# ANALOGv1_4.net
KiCad netlist of a schematic drawn in Altium Designer
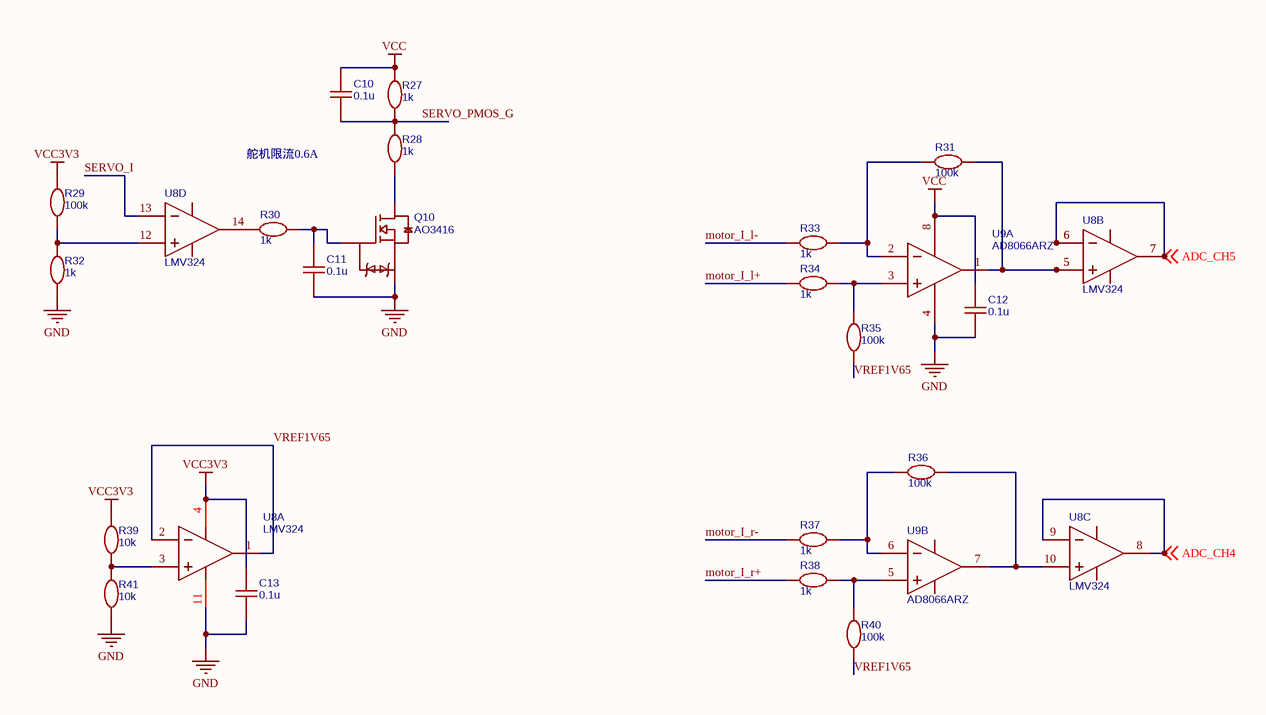
[diagram p0: ANALOGv1.4.SchDoc]

(export (version "E")
  (design (tool "Eeschema 10.0.6"))
  (components
    (comp (ref "C10")
      (value "0.1u")
      (footprint "C0603")
      (fields (field (name "CONTRIBUTOR") "LCEDA_Lib"))
      (libsource (lib "JLC") (part "C0603"))
    )
    (comp (ref "C11")
      (value "0.1u")
      (footprint "C0603")
      (fields (field (name "CONTRIBUTOR") "LCEDA_Lib"))
      (libsource (lib "JLC") (part "C0603"))
    )
    (comp (ref "C12")
      (value "0.1u")
      (footprint "C0603")
      (fields (field (name "CONTRIBUTOR") "LCEDA_Lib"))
      (libsource (lib "JLC") (part "C0603"))
    )
    (comp (ref "C13")
      (value "0.1u")
      (footprint "C0603")
      (fields (field (name "CONTRIBUTOR") "LCEDA_Lib"))
      (libsource (lib "JLC") (part "C0603"))
    )
    (comp (ref "Q10")
      (value "AO3416")
      (footprint "SOT-23-3_L2.9-W1.6-P1.90-LS2.8-BR")
      (fields (field (name "BOM_SUPPLIER PART") "C43307"))
      (libsource (lib "JLC") (part "AO3416"))
    )
    (comp (ref "R27")
      (value "1k")
      (footprint "R0603")
      (fields (field (name "CONTRIBUTOR") "LCEDA_Lib"))
      (libsource (lib "JLC") (part "R0603"))
    )
    (comp (ref "R28")
      (value "1k")
      (footprint "R0603")
      (fields (field (name "CONTRIBUTOR") "LCEDA_Lib"))
      (libsource (lib "JLC") (part "R0603"))
    )
    (comp (ref "R29")
      (value "100k")
      (footprint "R0603")
      (fields (field (name "CONTRIBUTOR") "LCEDA_Lib"))
      (libsource (lib "JLC") (part "R0603"))
    )
    (comp (ref "R30")
      (value "1k")
      (footprint "R0603")
      (fields (field (name "CONTRIBUTOR") "LCEDA_Lib"))
      (libsource (lib "JLC") (part "R0603"))
    )
    (comp (ref "R31")
      (value "100k")
      (footprint "R0603")
      (fields (field (name "CONTRIBUTOR") "LCEDA_Lib"))
      (libsource (lib "JLC") (part "R0603"))
    )
    (comp (ref "R32")
      (value "1k")
      (footprint "R0603")
      (fields (field (name "CONTRIBUTOR") "LCEDA_Lib"))
      (libsource (lib "JLC") (part "R0603"))
    )
    (comp (ref "R33")
      (value "1k")
      (footprint "R0603")
      (fields (field (name "CONTRIBUTOR") "LCEDA_Lib"))
      (libsource (lib "JLC") (part "R0603"))
    )
    (comp (ref "R34")
      (value "1k")
      (footprint "R0603")
      (fields (field (name "CONTRIBUTOR") "LCEDA_Lib"))
      (libsource (lib "JLC") (part "R0603"))
    )
    (comp (ref "R35")
      (value "100k")
      (footprint "R0603")
      (fields (field (name "CONTRIBUTOR") "LCEDA_Lib"))
      (libsource (lib "JLC") (part "R0603"))
    )
    (comp (ref "R36")
      (value "100k")
      (footprint "R0603")
      (fields (field (name "CONTRIBUTOR") "LCEDA_Lib"))
      (libsource (lib "JLC") (part "R0603"))
    )
    (comp (ref "R37")
      (value "1k")
      (footprint "R0603")
      (fields (field (name "CONTRIBUTOR") "LCEDA_Lib"))
      (libsource (lib "JLC") (part "R0603"))
    )
    (comp (ref "R38")
      (value "1k")
      (footprint "R0603")
      (fields (field (name "CONTRIBUTOR") "LCEDA_Lib"))
      (libsource (lib "JLC") (part "R0603"))
    )
    (comp (ref "R39")
      (value "10k")
      (footprint "R0603")
      (fields (field (name "CONTRIBUTOR") "LCEDA_Lib"))
      (libsource (lib "JLC") (part "R0603"))
    )
    (comp (ref "R40")
      (value "100k")
      (footprint "R0603")
      (fields (field (name "CONTRIBUTOR") "LCEDA_Lib"))
      (libsource (lib "JLC") (part "R0603"))
    )
    (comp (ref "R41")
      (value "10k")
      (footprint "R0603")
      (fields (field (name "CONTRIBUTOR") "LCEDA_Lib"))
      (libsource (lib "JLC") (part "R0603"))
    )
    (comp (ref "U8")
      (value "LMV324")
      (footprint "SOP-14_L8.6-W3.9-P1.27-LS6.0-BL")
      (fields (field (name "BOM_SUPPLIER PART") "C395458") (field (name "SUBPART_NO") "1"))
      (libsource (lib "") (part "LMV324_1"))
    )
    (comp (ref "U9")
      (value "AD8066ARZ")
      (footprint "SOIC-8_L5.0-W4.0-P1.27-LS6.0-BL")
      (fields (field (name "BOM_SUPPLIER PART") "C9647") (field (name "SUBPART_NO") "1"))
      (libsource (lib "JLC") (part "AD8066ARZ"))
    )
  )
  (nets
    (net (code "1") (name "/SERVO_I") (class "Default")
      (node (ref "U8") (pin "13") (pinfunction "4IN-_13") (pintype "passive"))
    )
    (net (code "2") (name "/SERVO_PMOS_G") (class "Default")
      (node (ref "C10") (pin "1") (pinfunction "1_1") (pintype "passive"))
      (node (ref "R27") (pin "1") (pinfunction "1_1") (pintype "passive"))
      (node (ref "R28") (pin "2") (pinfunction "2_2") (pintype "passive"))
    )
    (net (code "3") (name "/VREF1V65") (class "Default")
      (node (ref "R35") (pin "1") (pinfunction "1_1") (pintype "passive"))
      (node (ref "R40") (pin "1") (pinfunction "1_1") (pintype "passive"))
      (node (ref "U8") (pin "1") (pinfunction "1OUT_1") (pintype "passive"))
      (node (ref "U8") (pin "2") (pinfunction "1IN-_2") (pintype "passive"))
    )
    (net (code "4") (name "/motor_I_l+") (class "Default")
      (node (ref "R34") (pin "1") (pinfunction "1_1") (pintype "passive"))
    )
    (net (code "5") (name "/motor_I_l-") (class "Default")
      (node (ref "R33") (pin "1") (pinfunction "1_1") (pintype "passive"))
    )
    (net (code "6") (name "/motor_I_r+") (class "Default")
      (node (ref "R38") (pin "1") (pinfunction "1_1") (pintype "passive"))
    )
    (net (code "7") (name "/motor_I_r-") (class "Default")
      (node (ref "R37") (pin "1") (pinfunction "1_1") (pintype "passive"))
    )
    (net (code "8") (name "ADC_CH4") (class "Default")
      (node (ref "U8") (pin "8") (pinfunction "3OUT_8") (pintype "passive"))
      (node (ref "U8") (pin "9") (pinfunction "3IN-_9") (pintype "passive"))
    )
    (net (code "9") (name "ADC_CH5") (class "Default")
      (node (ref "U8") (pin "6") (pinfunction "2IN-_6") (pintype "passive"))
      (node (ref "U8") (pin "7") (pinfunction "2OUT_7") (pintype "passive"))
    )
    (net (code "10") (name "GND") (class "Default")
      (node (ref "C11") (pin "1") (pinfunction "1_1") (pintype "passive"))
      (node (ref "C12") (pin "1") (pinfunction "1_1") (pintype "passive"))
      (node (ref "C13") (pin "1") (pinfunction "1_1") (pintype "passive"))
      (node (ref "Q10") (pin "2") (pinfunction "S_2") (pintype "passive"))
      (node (ref "R32") (pin "1") (pinfunction "1_1") (pintype "passive"))
      (node (ref "R41") (pin "1") (pinfunction "1_1") (pintype "passive"))
      (node (ref "U8") (pin "11") (pinfunction "GND_11") (pintype "passive"))
      (node (ref "U9") (pin "4") (pinfunction "-VS_4") (pintype "passive"))
    )
    (net (code "11") (name "Net-(Q10-D)") (class "Default")
      (node (ref "Q10") (pin "3") (pinfunction "D_3") (pintype "passive"))
      (node (ref "R28") (pin "1") (pinfunction "1_1") (pintype "passive"))
    )
    (net (code "12") (name "Net-(Q10-G)") (class "Default")
      (node (ref "C11") (pin "2") (pinfunction "2_2") (pintype "passive"))
      (node (ref "Q10") (pin "1") (pinfunction "G_1") (pintype "passive"))
      (node (ref "R30") (pin "2") (pinfunction "2_2") (pintype "passive"))
    )
    (net (code "13") (name "Net-(U8A-1IN+)") (class "Default")
      (node (ref "R39") (pin "1") (pinfunction "1_1") (pintype "passive"))
      (node (ref "R41") (pin "2") (pinfunction "2_2") (pintype "passive"))
      (node (ref "U8") (pin "3") (pinfunction "1IN+_3") (pintype "passive"))
    )
    (net (code "14") (name "Net-(U8B-2IN+)") (class "Default")
      (node (ref "R31") (pin "2") (pinfunction "2_2") (pintype "passive"))
      (node (ref "U8") (pin "5") (pinfunction "2IN+_5") (pintype "passive"))
      (node (ref "U9") (pin "1") (pinfunction "VOUT_1_1") (pintype "passive"))
    )
    (net (code "15") (name "Net-(U8C-3IN+)") (class "Default")
      (node (ref "R36") (pin "1") (pinfunction "1_1") (pintype "passive"))
      (node (ref "U8") (pin "10") (pinfunction "3IN+_10") (pintype "passive"))
      (node (ref "U9") (pin "7") (pinfunction "VOUT_2_7") (pintype "passive"))
    )
    (net (code "16") (name "Net-(U8D-4IN+)") (class "Default")
      (node (ref "R29") (pin "1") (pinfunction "1_1") (pintype "passive"))
      (node (ref "R32") (pin "2") (pinfunction "2_2") (pintype "passive"))
      (node (ref "U8") (pin "12") (pinfunction "4IN+_12") (pintype "passive"))
    )
    (net (code "17") (name "Net-(U8D-4OUT)") (class "Default")
      (node (ref "R30") (pin "1") (pinfunction "1_1") (pintype "passive"))
      (node (ref "U8") (pin "14") (pinfunction "4OUT_14") (pintype "passive"))
    )
    (net (code "18") (name "Net-(U9A-+IN_1)") (class "Default")
      (node (ref "R34") (pin "2") (pinfunction "2_2") (pintype "passive"))
      (node (ref "R35") (pin "2") (pinfunction "2_2") (pintype "passive"))
      (node (ref "U9") (pin "3") (pinfunction "+IN_1_3") (pintype "passive"))
    )
    (net (code "19") (name "Net-(U9A--IN_1)") (class "Default")
      (node (ref "R31") (pin "1") (pinfunction "1_1") (pintype "passive"))
      (node (ref "R33") (pin "2") (pinfunction "2_2") (pintype "passive"))
      (node (ref "U9") (pin "2") (pinfunction "-IN_1_2") (pintype "passive"))
    )
    (net (code "20") (name "Net-(U9B-+IN_2)") (class "Default")
      (node (ref "R38") (pin "2") (pinfunction "2_2") (pintype "passive"))
      (node (ref "R40") (pin "2") (pinfunction "2_2") (pintype "passive"))
      (node (ref "U9") (pin "5") (pinfunction "+IN_2_5") (pintype "passive"))
    )
    (net (code "21") (name "Net-(U9B--IN_2)") (class "Default")
      (node (ref "R36") (pin "2") (pinfunction "2_2") (pintype "passive"))
      (node (ref "R37") (pin "2") (pinfunction "2_2") (pintype "passive"))
      (node (ref "U9") (pin "6") (pinfunction "-IN_2_6") (pintype "passive"))
    )
    (net (code "22") (name "VCC") (class "Default")
      (node (ref "C10") (pin "2") (pinfunction "2_2") (pintype "passive"))
      (node (ref "C12") (pin "2") (pinfunction "2_2") (pintype "passive"))
      (node (ref "R27") (pin "2") (pinfunction "2_2") (pintype "passive"))
      (node (ref "U9") (pin "8") (pinfunction "+VS_8") (pintype "passive"))
    )
    (net (code "23") (name "VCC3V3") (class "Default")
      (node (ref "C13") (pin "2") (pinfunction "2_2") (pintype "passive"))
      (node (ref "R29") (pin "2") (pinfunction "2_2") (pintype "passive"))
      (node (ref "R39") (pin "2") (pinfunction "2_2") (pintype "passive"))
      (node (ref "U8") (pin "4") (pinfunction "VCC_4") (pintype "passive"))
    )
  )
)
